# BURPG_accelerometer_v1.net
KiCad netlist of a schematic drawn in Altium Designer
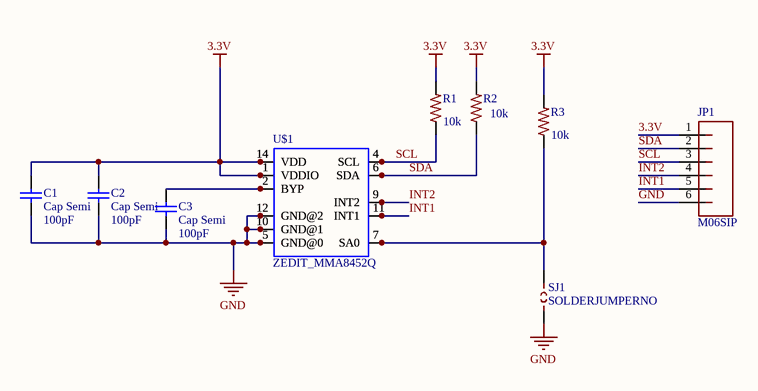
[diagram p0: BURPG_accelerometer_v1.SchDoc]

(export (version "E")
  (design (tool "Eeschema 10.0.6"))
  (components
    (comp (ref "C1")
      (value "Cap Semi")
      (footprint "1608[0603]")
      (description "Capacitor (Semiconductor SIM Model)")
      (fields (field (name "ALTIUM_VALUE") "100pF") (field (name "PUBLISHER") "Altium Limited"))
      (libsource (lib "Miscellaneous Devices") (part "Cap Semi"))
    )
    (comp (ref "C2")
      (value "Cap Semi")
      (footprint "1608[0603]")
      (description "Capacitor (Semiconductor SIM Model)")
      (fields (field (name "ALTIUM_VALUE") "100pF") (field (name "PUBLISHER") "Altium Limited"))
      (libsource (lib "Miscellaneous Devices") (part "Cap Semi"))
    )
    (comp (ref "C3")
      (value "Cap Semi")
      (footprint "1608[0603]")
      (description "Capacitor (Semiconductor SIM Model)")
      (fields (field (name "ALTIUM_VALUE") "100pF") (field (name "PUBLISHER") "Altium Limited"))
      (libsource (lib "Miscellaneous Devices") (part "Cap Semi"))
    )
    (comp (ref "JP1")
      (value "M06SIP")
      (footprint "1X06")
      (libsource (lib "MMA8452Q_Breakoutv10_zv1_1") (part "M06SIP"))
    )
    (comp (ref "R1")
      (value "10k")
      (footprint "0603-RES")
      (libsource (lib "MMA8452Q_Breakoutv10_zv1_1") (part "10K-1%RES-00824"))
    )
    (comp (ref "R2")
      (value "10k")
      (footprint "0603-RES")
      (libsource (lib "MMA8452Q_Breakoutv10_zv1_1") (part "10K-1%RES-00824"))
    )
    (comp (ref "R3")
      (value "10k")
      (footprint "0603-RES")
      (libsource (lib "MMA8452Q_Breakoutv10_zv1_1") (part "10K-1%RES-00824"))
    )
    (comp (ref "SJ1")
      (value "SOLDERJUMPERNO")
      (footprint "SJ_2S-NO")
      (libsource (lib "MMA8452Q_Breakoutv10_zv1_1") (part "SOLDERJUMPERNO"))
    )
    (comp (ref "U$1")
      (value "ZEDIT_MMA8452Q")
      (footprint "2mma_accle_lib_test:ZEDIT_MMASENSOR")
      (libsource (lib "2mma_accle_lib_test_1") (part "ZEDIT_MMA8452Q"))
    )
  )
  (nets
    (net (code "1") (name "/INT1") (class "Default")
      (node (ref "JP1") (pin "5") (pinfunction "5_5") (pintype "passive"))
      (node (ref "U$1") (pin "11") (pinfunction "INT1_11") (pintype "passive"))
    )
    (net (code "2") (name "/INT2") (class "Default")
      (node (ref "JP1") (pin "4") (pinfunction "4_4") (pintype "passive"))
      (node (ref "U$1") (pin "9") (pinfunction "INT2_9") (pintype "passive"))
    )
    (net (code "3") (name "/SCL") (class "Default")
      (node (ref "JP1") (pin "3") (pinfunction "3_3") (pintype "passive"))
      (node (ref "R1") (pin "1") (pinfunction "1_1") (pintype "passive"))
      (node (ref "U$1") (pin "4") (pinfunction "SCL_4") (pintype "passive"))
    )
    (net (code "4") (name "/SDA") (class "Default")
      (node (ref "JP1") (pin "2") (pinfunction "2_2") (pintype "passive"))
      (node (ref "R2") (pin "1") (pinfunction "1_1") (pintype "passive"))
      (node (ref "U$1") (pin "6") (pinfunction "SDA_6") (pintype "passive"))
    )
    (net (code "5") (name "3.3V") (class "Default")
      (node (ref "C1") (pin "2") (pinfunction "2_2") (pintype "passive"))
      (node (ref "C2") (pin "2") (pinfunction "2_2") (pintype "passive"))
      (node (ref "JP1") (pin "1") (pinfunction "1_1") (pintype "passive"))
      (node (ref "R1") (pin "2") (pinfunction "2_2") (pintype "passive"))
      (node (ref "R2") (pin "2") (pinfunction "2_2") (pintype "passive"))
      (node (ref "R3") (pin "2") (pinfunction "2_2") (pintype "passive"))
      (node (ref "U$1") (pin "1") (pinfunction "VDDIO_1") (pintype "passive"))
      (node (ref "U$1") (pin "14") (pinfunction "VDD_14") (pintype "passive"))
    )
    (net (code "6") (name "GND") (class "Default")
      (node (ref "C1") (pin "1") (pinfunction "1_1") (pintype "passive"))
      (node (ref "C2") (pin "1") (pinfunction "1_1") (pintype "passive"))
      (node (ref "C3") (pin "1") (pinfunction "1_1") (pintype "passive"))
      (node (ref "JP1") (pin "6") (pinfunction "6_6") (pintype "passive"))
      (node (ref "SJ1") (pin "1") (pinfunction "1_1") (pintype "passive"))
      (node (ref "U$1") (pin "10") (pinfunction "GND@1_10") (pintype "passive"))
      (node (ref "U$1") (pin "12") (pinfunction "GND@2_12") (pintype "passive"))
      (node (ref "U$1") (pin "5") (pinfunction "GND@0_5") (pintype "passive"))
    )
    (net (code "7") (name "Net-(U$1-BYP)") (class "Default")
      (node (ref "C3") (pin "2") (pinfunction "2_2") (pintype "passive"))
      (node (ref "U$1") (pin "2") (pinfunction "BYP_2") (pintype "passive"))
    )
    (net (code "8") (name "Net-(U$1-SA0)") (class "Default")
      (node (ref "R3") (pin "1") (pinfunction "1_1") (pintype "passive"))
      (node (ref "SJ1") (pin "2") (pinfunction "2_2") (pintype "passive"))
      (node (ref "U$1") (pin "7") (pinfunction "SA0_7") (pintype "passive"))
    )
  )
)
